# DPort-ECT_Reference_Design.net
KiCad netlist of a schematic drawn in Altium Designer
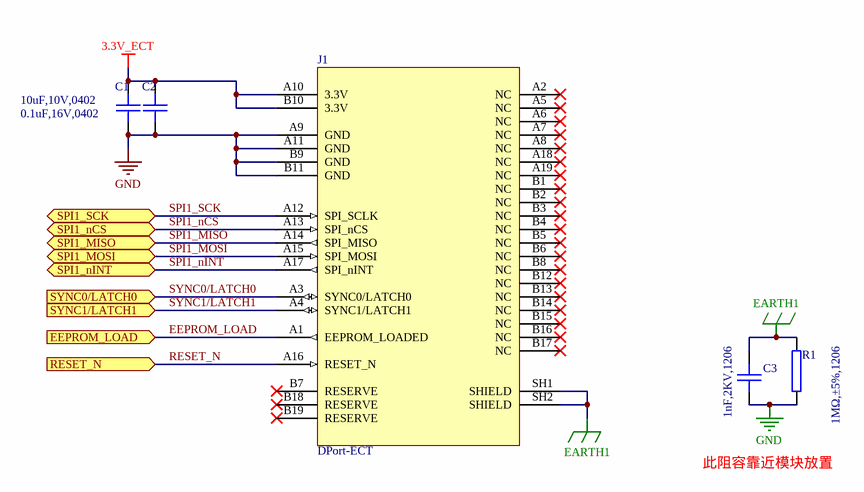
[diagram p0: DPort-ECT Reference Design.SchDoc]

(export (version "E")
  (design (tool "Eeschema 10.0.6"))
  (components
    (comp (ref "C1")
      (value "10uF,10V,0402")
      (footprint "0402C")
      (description "GRM155R61A106ME11D,0402,muRata,10uF,X5R,±20%,10V")
      (libsource (lib "ErpMaterialData-U9") (part "CAP1"))
    )
    (comp (ref "C2")
      (value "0.1uF,16V,0402")
      (footprint "0402C")
      (description "CC0402KRX7R7BB104,0402,YAGEO,0.1uF,X7R,±10%,16V,")
      (libsource (lib "ErpMaterialData-U9") (part "CAP1"))
    )
    (comp (ref "C3")
      (value "1nF,2KV,1206")
      (footprint "1206C")
      (description "CC1206KKX7RDBB102,1206,YAGEO,1nF,X7R,±10%,2KV,")
      (libsource (lib "ErpMaterialData-U9") (part "CAP1"))
    )
    (comp (ref "J1")
      (value "DPort-ECT")
      (footprint "DPort:DPORT-G")
      (libsource (lib "DPort-ECT") (part "DPort-ECT"))
    )
    (comp (ref "R1")
      (value "1MΩ,±5%,1206")
      (footprint "1206R")
      (description "RTT06105JTP,1206,RALEC,1MΩ,±5%,1/4W,")
      (libsource (lib "ErpMaterialData-U9") (part "RES2"))
    )
  )
  (nets
    (net (code "1") (name "/EEPROM_LOAD") (class "Default")
      (node (ref "J1") (pin "A1") (pinfunction "EEPROM_LOADED_A1") (pintype "output"))
    )
    (net (code "2") (name "/RESET_N") (class "Default")
      (node (ref "J1") (pin "A16") (pinfunction "RESET_N_A16") (pintype "input"))
    )
    (net (code "3") (name "/SPI1_MISO") (class "Default")
      (node (ref "J1") (pin "A14") (pinfunction "SPI_MISO_A14") (pintype "output"))
    )
    (net (code "4") (name "/SPI1_MOSI") (class "Default")
      (node (ref "J1") (pin "A15") (pinfunction "SPI_MOSI_A15") (pintype "input"))
    )
    (net (code "5") (name "/SPI1_SCK") (class "Default")
      (node (ref "J1") (pin "A12") (pinfunction "SPI_SCLK_A12") (pintype "input"))
    )
    (net (code "6") (name "/SPI1_nCS") (class "Default")
      (node (ref "J1") (pin "A13") (pinfunction "SPI_nCS_A13") (pintype "input"))
    )
    (net (code "7") (name "/SPI1_nINT") (class "Default")
      (node (ref "J1") (pin "A17") (pinfunction "SPI_nINT_A17") (pintype "output"))
    )
    (net (code "8") (name "/SYNC0{slash}LATCH0") (class "Default")
      (node (ref "J1") (pin "A3") (pinfunction "SYNC0/LATCH0_A3") (pintype "bidirectional"))
    )
    (net (code "9") (name "/SYNC1{slash}LATCH1") (class "Default")
      (node (ref "J1") (pin "A4") (pinfunction "SYNC1/LATCH1_A4") (pintype "bidirectional"))
    )
    (net (code "10") (name "3.3V_ECT") (class "Default")
      (node (ref "C1") (pin "1") (pinfunction "1_1") (pintype "passive"))
      (node (ref "C2") (pin "1") (pinfunction "1_1") (pintype "passive"))
      (node (ref "J1") (pin "A10") (pinfunction "3.3V_A10") (pintype "passive"))
      (node (ref "J1") (pin "B10") (pinfunction "3.3V_B10") (pintype "passive"))
    )
    (net (code "11") (name "EARTH1") (class "Default")
      (node (ref "C3") (pin "2") (pinfunction "2_2") (pintype "passive"))
      (node (ref "J1") (pin "SH1") (pinfunction "SHIELD_SH1") (pintype "passive"))
      (node (ref "J1") (pin "SH2") (pinfunction "SHIELD_SH2") (pintype "passive"))
      (node (ref "R1") (pin "2") (pinfunction "2_2") (pintype "passive"))
    )
    (net (code "12") (name "GND") (class "Default")
      (node (ref "C1") (pin "2") (pinfunction "2_2") (pintype "passive"))
      (node (ref "C2") (pin "2") (pinfunction "2_2") (pintype "passive"))
      (node (ref "C3") (pin "1") (pinfunction "1_1") (pintype "passive"))
      (node (ref "J1") (pin "A11") (pinfunction "GND_A11") (pintype "passive"))
      (node (ref "J1") (pin "A9") (pinfunction "GND_A9") (pintype "passive"))
      (node (ref "J1") (pin "B11") (pinfunction "GND_B11") (pintype "passive"))
      (node (ref "J1") (pin "B9") (pinfunction "GND_B9") (pintype "passive"))
      (node (ref "R1") (pin "1") (pinfunction "1_1") (pintype "passive"))
    )
    (net (code "13") (name "unconnected-(J1-NC-PadA2)") (class "Default")
      (node (ref "J1") (pin "A2") (pinfunction "NC_A2") (pintype "passive+no_connect"))
    )
    (net (code "14") (name "unconnected-(J1-NC-PadA5)") (class "Default")
      (node (ref "J1") (pin "A5") (pinfunction "NC_A5") (pintype "passive+no_connect"))
    )
    (net (code "15") (name "unconnected-(J1-NC-PadA6)") (class "Default")
      (node (ref "J1") (pin "A6") (pinfunction "NC_A6") (pintype "passive+no_connect"))
    )
    (net (code "16") (name "unconnected-(J1-NC-PadA7)") (class "Default")
      (node (ref "J1") (pin "A7") (pinfunction "NC_A7") (pintype "passive+no_connect"))
    )
    (net (code "17") (name "unconnected-(J1-NC-PadA8)") (class "Default")
      (node (ref "J1") (pin "A8") (pinfunction "NC_A8") (pintype "passive+no_connect"))
    )
    (net (code "18") (name "unconnected-(J1-NC-PadA18)") (class "Default")
      (node (ref "J1") (pin "A18") (pinfunction "NC_A18") (pintype "passive+no_connect"))
    )
    (net (code "19") (name "unconnected-(J1-NC-PadA19)") (class "Default")
      (node (ref "J1") (pin "A19") (pinfunction "NC_A19") (pintype "passive+no_connect"))
    )
    (net (code "20") (name "unconnected-(J1-NC-PadB1)") (class "Default")
      (node (ref "J1") (pin "B1") (pinfunction "NC_B1") (pintype "passive+no_connect"))
    )
    (net (code "21") (name "unconnected-(J1-NC-PadB2)") (class "Default")
      (node (ref "J1") (pin "B2") (pinfunction "NC_B2") (pintype "passive+no_connect"))
    )
    (net (code "22") (name "unconnected-(J1-NC-PadB3)") (class "Default")
      (node (ref "J1") (pin "B3") (pinfunction "NC_B3") (pintype "passive+no_connect"))
    )
    (net (code "23") (name "unconnected-(J1-NC-PadB4)") (class "Default")
      (node (ref "J1") (pin "B4") (pinfunction "NC_B4") (pintype "passive+no_connect"))
    )
    (net (code "24") (name "unconnected-(J1-NC-PadB5)") (class "Default")
      (node (ref "J1") (pin "B5") (pinfunction "NC_B5") (pintype "passive+no_connect"))
    )
    (net (code "25") (name "unconnected-(J1-NC-PadB6)") (class "Default")
      (node (ref "J1") (pin "B6") (pinfunction "NC_B6") (pintype "passive+no_connect"))
    )
    (net (code "26") (name "unconnected-(J1-NC-PadB8)") (class "Default")
      (node (ref "J1") (pin "B8") (pinfunction "NC_B8") (pintype "passive+no_connect"))
    )
    (net (code "27") (name "unconnected-(J1-NC-PadB12)") (class "Default")
      (node (ref "J1") (pin "B12") (pinfunction "NC_B12") (pintype "passive+no_connect"))
    )
    (net (code "28") (name "unconnected-(J1-NC-PadB13)") (class "Default")
      (node (ref "J1") (pin "B13") (pinfunction "NC_B13") (pintype "passive+no_connect"))
    )
    (net (code "29") (name "unconnected-(J1-NC-PadB14)") (class "Default")
      (node (ref "J1") (pin "B14") (pinfunction "NC_B14") (pintype "passive+no_connect"))
    )
    (net (code "30") (name "unconnected-(J1-NC-PadB15)") (class "Default")
      (node (ref "J1") (pin "B15") (pinfunction "NC_B15") (pintype "passive+no_connect"))
    )
    (net (code "31") (name "unconnected-(J1-NC-PadB16)") (class "Default")
      (node (ref "J1") (pin "B16") (pinfunction "NC_B16") (pintype "passive+no_connect"))
    )
    (net (code "32") (name "unconnected-(J1-NC-PadB17)") (class "Default")
      (node (ref "J1") (pin "B17") (pinfunction "NC_B17") (pintype "passive+no_connect"))
    )
    (net (code "33") (name "unconnected-(J1-RESERVE-PadB7)") (class "Default")
      (node (ref "J1") (pin "B7") (pinfunction "RESERVE_B7") (pintype "power_in+no_connect"))
    )
    (net (code "34") (name "unconnected-(J1-RESERVE-PadB18)") (class "Default")
      (node (ref "J1") (pin "B18") (pinfunction "RESERVE_B18") (pintype "passive+no_connect"))
    )
    (net (code "35") (name "unconnected-(J1-RESERVE-PadB19)") (class "Default")
      (node (ref "J1") (pin "B19") (pinfunction "RESERVE_B19") (pintype "passive+no_connect"))
    )
  )
)
